# Schematic.net
KiCad netlist of a schematic drawn in EAGLE
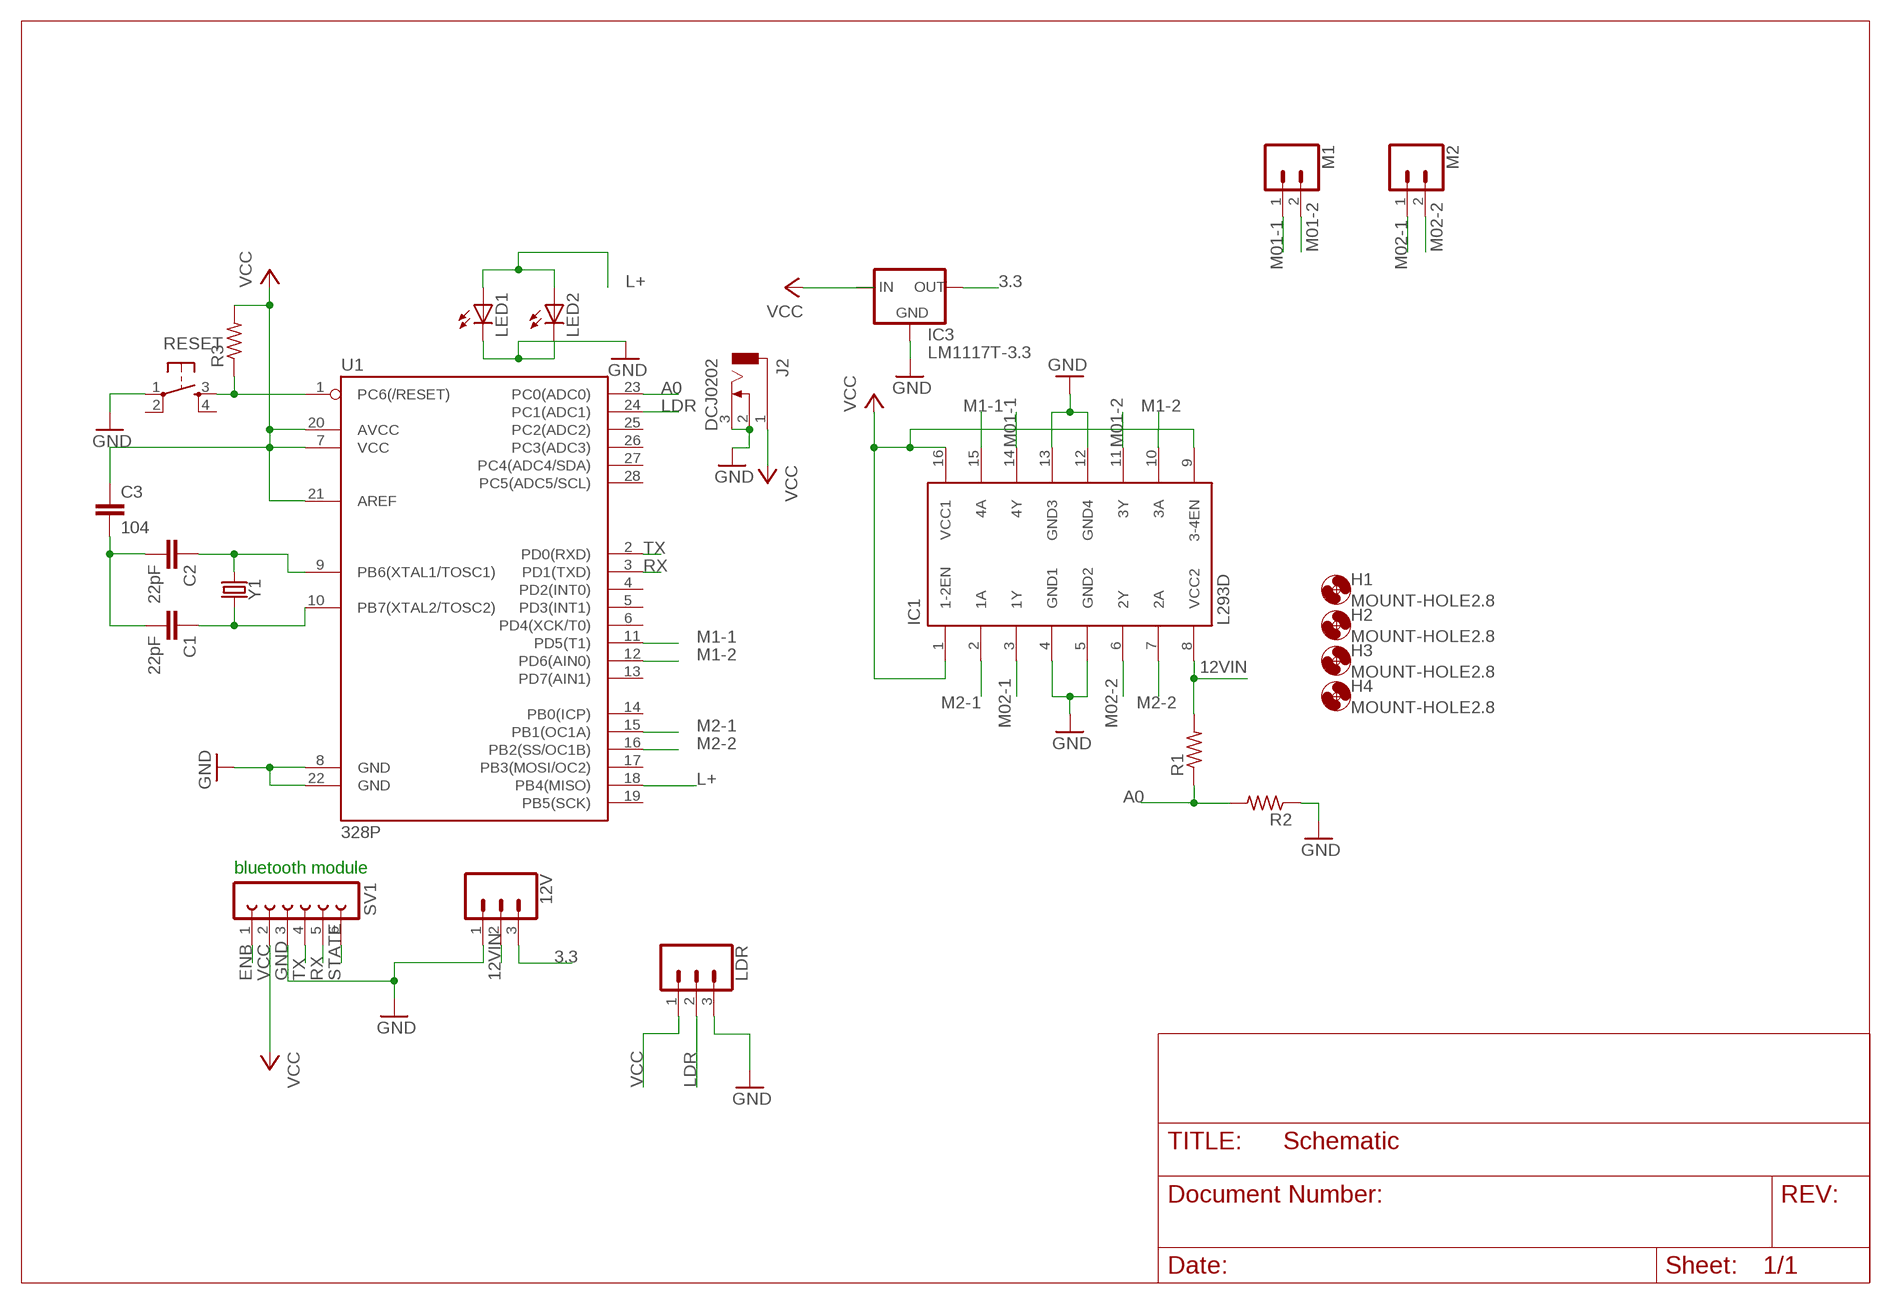
[diagram p0: schematic, sheet 1]

(export (version "E")
  (design (tool "Eeschema 10.0.6"))
  (components
    (comp (ref "12V")
      (value "CONN_03")
      (footprint "eagle-import:1X03")
      (libsource (lib "eagle-import") (part "CONN_03"))
    )
    (comp (ref "C1")
      (value "22pF")
      (footprint "eagle-import:CAP-PTH-2.54")
      (libsource (lib "eagle-import") (part "22PF-PTH-2.54MM-200V-5%"))
    )
    (comp (ref "C2")
      (value "22pF")
      (footprint "eagle-import:CAP-PTH-2.54")
      (libsource (lib "eagle-import") (part "22PF-PTH-2.54MM-200V-5%"))
    )
    (comp (ref "C3")
      (value "104")
      (footprint "eagle-import:CAP-PTH-2.54")
      (libsource (lib "eagle-import") (part "22PF-PTH-2.54MM-200V-5%"))
    )
    (comp (ref "H1")
      (value "MOUNT-HOLE2.8")
      (footprint "eagle-import:2,8")
      (libsource (lib "eagle-import") (part "MOUNT-HOLE2.8"))
    )
    (comp (ref "H2")
      (value "MOUNT-HOLE2.8")
      (footprint "eagle-import:2,8")
      (libsource (lib "eagle-import") (part "MOUNT-HOLE2.8"))
    )
    (comp (ref "H3")
      (value "MOUNT-HOLE2.8")
      (footprint "eagle-import:2,8")
      (libsource (lib "eagle-import") (part "MOUNT-HOLE2.8"))
    )
    (comp (ref "H4")
      (value "MOUNT-HOLE2.8")
      (footprint "eagle-import:2,8")
      (libsource (lib "eagle-import") (part "MOUNT-HOLE2.8"))
    )
    (comp (ref "IC1")
      (value "L293D")
      (footprint "eagle-import:DIL16")
      (libsource (lib "eagle-import") (part "L293D"))
    )
    (comp (ref "IC3")
      (value "LM1117T-3.3")
      (footprint "eagle-import:TO220")
      (libsource (lib "eagle-import") (part "LM1117T-3.3"))
    )
    (comp (ref "J2")
      (value "DCJ0202")
      (footprint "eagle-import:DCJ0202")
      (libsource (lib "eagle-import") (part "DCJ0202"))
    )
    (comp (ref "LDR")
      (value "CONN_03")
      (footprint "eagle-import:1X03")
      (libsource (lib "eagle-import") (part "CONN_03"))
    )
    (comp (ref "LED1")
      (value "LED5MM")
      (footprint "eagle-import:LED5MM")
      (libsource (lib "eagle-import") (part "LED5MM"))
    )
    (comp (ref "LED2")
      (value "LED5MM")
      (footprint "eagle-import:LED5MM")
      (libsource (lib "eagle-import") (part "LED5MM"))
    )
    (comp (ref "M1")
      (value "CONN_023.5MM")
      (footprint "eagle-import:SCREWTERMINAL-3.5MM-2")
      (libsource (lib "eagle-import") (part "CONN_023.5MM"))
    )
    (comp (ref "M2")
      (value "CONN_023.5MM")
      (footprint "eagle-import:SCREWTERMINAL-3.5MM-2")
      (libsource (lib "eagle-import") (part "CONN_023.5MM"))
    )
    (comp (ref "R1")
      (value "R-US_0204/7")
      (footprint "eagle-import:0204_7")
      (libsource (lib "eagle-import") (part "R-US_0204/7"))
    )
    (comp (ref "R2")
      (value "R-US_0204/7")
      (footprint "eagle-import:0204_7")
      (libsource (lib "eagle-import") (part "R-US_0204/7"))
    )
    (comp (ref "R3")
      (value "R-US_0204/7")
      (footprint "eagle-import:0204_7")
      (libsource (lib "eagle-import") (part "R-US_0204/7"))
    )
    (comp (ref "RESET")
      (value "TAC_SWITCHPTH")
      (footprint "eagle-import:TACTILE-PTH")
      (libsource (lib "eagle-import") (part "TAC_SWITCHPTH"))
    )
    (comp (ref "SV1")
      (value "FE06-1")
      (footprint "eagle-import:FE06")
      (libsource (lib "eagle-import") (part "FE06-1"))
    )
    (comp (ref "U1")
      (value "328P")
      (footprint "eagle-import:DIP28")
      (libsource (lib "eagle-import") (part "ATMEGA328P_PDIP"))
    )
    (comp (ref "Y1")
      (value "CRYSTALPTH-HC49US")
      (footprint "eagle-import:HC49US")
      (libsource (lib "eagle-import") (part "CRYSTALPTH-HC49US"))
    )
  )
  (nets
    (net (code "1") (name "/3.3") (class "Default")
      (node (ref "12V") (pin "3") (pinfunction "3_3") (pintype "passive"))
      (node (ref "IC3") (pin "2") (pinfunction "OUT_2") (pintype "passive"))
    )
    (net (code "2") (name "/12VIN") (class "Default")
      (node (ref "12V") (pin "2") (pinfunction "2_2") (pintype "passive"))
      (node (ref "IC1") (pin "8") (pinfunction "VCC2_8") (pintype "power_in"))
      (node (ref "R1") (pin "2") (pinfunction "2_2") (pintype "passive"))
    )
    (net (code "3") (name "/A0") (class "Default")
      (node (ref "R1") (pin "1") (pinfunction "1_1") (pintype "passive"))
      (node (ref "R2") (pin "2") (pinfunction "2_2") (pintype "passive"))
      (node (ref "U1") (pin "23") (pinfunction "PC0(ADC0)_23") (pintype "bidirectional"))
    )
    (net (code "4") (name "/ENB") (class "Default")
      (node (ref "SV1") (pin "1") (pinfunction "1_1") (pintype "passive"))
    )
    (net (code "5") (name "/L+") (class "Default")
      (node (ref "LED1") (pin "A") (pinfunction "A_A") (pintype "passive"))
      (node (ref "LED2") (pin "A") (pinfunction "A_A") (pintype "passive"))
      (node (ref "U1") (pin "18") (pinfunction "PB4(MISO)_18") (pintype "bidirectional"))
    )
    (net (code "6") (name "/LDR") (class "Default")
      (node (ref "LDR") (pin "2") (pinfunction "2_2") (pintype "passive"))
      (node (ref "U1") (pin "24") (pinfunction "PC1(ADC1)_24") (pintype "bidirectional"))
    )
    (net (code "7") (name "/M01-1") (class "Default")
      (node (ref "IC1") (pin "14") (pinfunction "4Y_14") (pintype "output"))
      (node (ref "M1") (pin "1") (pinfunction "1_1") (pintype "passive"))
    )
    (net (code "8") (name "/M1-1") (class "Default")
      (node (ref "IC1") (pin "15") (pinfunction "4A_15") (pintype "input"))
      (node (ref "U1") (pin "11") (pinfunction "PD5(T1)_11") (pintype "bidirectional"))
    )
    (net (code "9") (name "/M01-2") (class "Default")
      (node (ref "IC1") (pin "11") (pinfunction "3Y_11") (pintype "output"))
      (node (ref "M1") (pin "2") (pinfunction "2_2") (pintype "passive"))
    )
    (net (code "10") (name "/M1-2") (class "Default")
      (node (ref "IC1") (pin "10") (pinfunction "3A_10") (pintype "input"))
      (node (ref "U1") (pin "12") (pinfunction "PD6(AIN0)_12") (pintype "bidirectional"))
    )
    (net (code "11") (name "/M02-1") (class "Default")
      (node (ref "IC1") (pin "3") (pinfunction "1Y_3") (pintype "output"))
      (node (ref "M2") (pin "1") (pinfunction "1_1") (pintype "passive"))
    )
    (net (code "12") (name "/M2-1") (class "Default")
      (node (ref "IC1") (pin "2") (pinfunction "1A_2") (pintype "input"))
      (node (ref "U1") (pin "15") (pinfunction "PB1(OC1A)_15") (pintype "bidirectional"))
    )
    (net (code "13") (name "/M02-2") (class "Default")
      (node (ref "IC1") (pin "6") (pinfunction "2Y_6") (pintype "output"))
      (node (ref "M2") (pin "2") (pinfunction "2_2") (pintype "passive"))
    )
    (net (code "14") (name "/M2-2") (class "Default")
      (node (ref "IC1") (pin "7") (pinfunction "2A_7") (pintype "input"))
      (node (ref "U1") (pin "16") (pinfunction "PB2(SS/OC1B)_16") (pintype "bidirectional"))
    )
    (net (code "15") (name "/RX") (class "Default")
      (node (ref "SV1") (pin "5") (pinfunction "5_5") (pintype "passive"))
      (node (ref "U1") (pin "3") (pinfunction "PD1(TXD)_3") (pintype "bidirectional"))
    )
    (net (code "16") (name "/STATE") (class "Default")
      (node (ref "SV1") (pin "6") (pinfunction "6_6") (pintype "passive"))
    )
    (net (code "17") (name "/TX") (class "Default")
      (node (ref "SV1") (pin "4") (pinfunction "4_4") (pintype "passive"))
      (node (ref "U1") (pin "2") (pinfunction "PD0(RXD)_2") (pintype "bidirectional"))
    )
    (net (code "18") (name "GND") (class "Default")
      (node (ref "12V") (pin "1") (pinfunction "1_1") (pintype "passive"))
      (node (ref "IC1") (pin "12") (pinfunction "GND4_12") (pintype "power_in"))
      (node (ref "IC1") (pin "13") (pinfunction "GND3_13") (pintype "power_in"))
      (node (ref "IC1") (pin "4") (pinfunction "GND1_4") (pintype "power_in"))
      (node (ref "IC1") (pin "5") (pinfunction "GND2_5") (pintype "power_in"))
      (node (ref "IC3") (pin "1") (pinfunction "GND_1") (pintype "input"))
      (node (ref "J2") (pin "2") (pinfunction "2_2") (pintype "passive"))
      (node (ref "J2") (pin "3") (pinfunction "3_3") (pintype "passive"))
      (node (ref "LDR") (pin "3") (pinfunction "3_3") (pintype "passive"))
      (node (ref "LED1") (pin "K") (pinfunction "C_K") (pintype "passive"))
      (node (ref "LED2") (pin "K") (pinfunction "C_K") (pintype "passive"))
      (node (ref "R2") (pin "1") (pinfunction "1_1") (pintype "passive"))
      (node (ref "RESET") (pin "1") (pinfunction "1_1") (pintype "passive"))
      (node (ref "SV1") (pin "3") (pinfunction "3_3") (pintype "passive"))
      (node (ref "U1") (pin "22") (pinfunction "GND_22") (pintype "bidirectional"))
      (node (ref "U1") (pin "8") (pinfunction "GND_8") (pintype "bidirectional"))
    )
    (net (code "19") (name "Net-(C1-Pad2)") (class "Default")
      (node (ref "C1") (pin "2") (pinfunction "2_2") (pintype "passive"))
      (node (ref "C2") (pin "2") (pinfunction "2_2") (pintype "passive"))
      (node (ref "C3") (pin "2") (pinfunction "2_2") (pintype "passive"))
    )
    (net (code "20") (name "Net-(U1-PB6(XTAL1{slash}TOSC1))") (class "Default")
      (node (ref "C2") (pin "1") (pinfunction "1_1") (pintype "passive"))
      (node (ref "U1") (pin "9") (pinfunction "PB6(XTAL1/TOSC1)_9") (pintype "bidirectional"))
      (node (ref "Y1") (pin "1") (pinfunction "1_1") (pintype "passive"))
    )
    (net (code "21") (name "Net-(U1-PB7(XTAL2{slash}TOSC2))") (class "Default")
      (node (ref "C1") (pin "1") (pinfunction "1_1") (pintype "passive"))
      (node (ref "U1") (pin "10") (pinfunction "PB7(XTAL2/TOSC2)_10") (pintype "bidirectional"))
      (node (ref "Y1") (pin "2") (pinfunction "2_2") (pintype "passive"))
    )
    (net (code "22") (name "Net-(U1-PC6({slash}RESET))") (class "Default")
      (node (ref "R3") (pin "1") (pinfunction "1_1") (pintype "passive"))
      (node (ref "RESET") (pin "3") (pinfunction "3_3") (pintype "passive"))
      (node (ref "U1") (pin "1") (pinfunction "PC6(/RESET)_1") (pintype "bidirectional"))
    )
    (net (code "23") (name "VCC") (class "Default")
      (node (ref "C3") (pin "1") (pinfunction "1_1") (pintype "passive"))
      (node (ref "IC1") (pin "1") (pinfunction "1-2EN_1") (pintype "input"))
      (node (ref "IC1") (pin "16") (pinfunction "VCC1_16") (pintype "power_in"))
      (node (ref "IC1") (pin "9") (pinfunction "3-4EN_9") (pintype "input"))
      (node (ref "IC3") (pin "3") (pinfunction "IN_3") (pintype "input"))
      (node (ref "J2") (pin "1") (pinfunction "1_1") (pintype "passive"))
      (node (ref "LDR") (pin "1") (pinfunction "1_1") (pintype "passive"))
      (node (ref "R3") (pin "2") (pinfunction "2_2") (pintype "passive"))
      (node (ref "SV1") (pin "2") (pinfunction "2_2") (pintype "passive"))
      (node (ref "U1") (pin "20") (pinfunction "AVCC_20") (pintype "bidirectional"))
      (node (ref "U1") (pin "21") (pinfunction "AREF_21") (pintype "bidirectional"))
      (node (ref "U1") (pin "7") (pinfunction "VCC_7") (pintype "bidirectional"))
    )
    (net (code "24") (name "unconnected-(RESET-Pad2)") (class "Default")
      (node (ref "RESET") (pin "2") (pinfunction "2_2") (pintype "passive"))
    )
    (net (code "25") (name "unconnected-(RESET-Pad4)") (class "Default")
      (node (ref "RESET") (pin "4") (pinfunction "4_4") (pintype "passive"))
    )
    (net (code "26") (name "unconnected-(U1-PB0(ICP)-Pad14)") (class "Default")
      (node (ref "U1") (pin "14") (pinfunction "PB0(ICP)_14") (pintype "bidirectional"))
    )
    (net (code "27") (name "unconnected-(U1-PB3(MOSI{slash}OC2)-Pad17)") (class "Default")
      (node (ref "U1") (pin "17") (pinfunction "PB3(MOSI/OC2)_17") (pintype "bidirectional"))
    )
    (net (code "28") (name "unconnected-(U1-PB5(SCK)-Pad19)") (class "Default")
      (node (ref "U1") (pin "19") (pinfunction "PB5(SCK)_19") (pintype "bidirectional"))
    )
    (net (code "29") (name "unconnected-(U1-PC2(ADC2)-Pad25)") (class "Default")
      (node (ref "U1") (pin "25") (pinfunction "PC2(ADC2)_25") (pintype "bidirectional"))
    )
    (net (code "30") (name "unconnected-(U1-PC3(ADC3)-Pad26)") (class "Default")
      (node (ref "U1") (pin "26") (pinfunction "PC3(ADC3)_26") (pintype "bidirectional"))
    )
    (net (code "31") (name "unconnected-(U1-PC4(ADC4{slash}SDA)-Pad27)") (class "Default")
      (node (ref "U1") (pin "27") (pinfunction "PC4(ADC4/SDA)_27") (pintype "bidirectional"))
    )
    (net (code "32") (name "unconnected-(U1-PC5(ADC5{slash}SCL)-Pad28)") (class "Default")
      (node (ref "U1") (pin "28") (pinfunction "PC5(ADC5/SCL)_28") (pintype "bidirectional"))
    )
    (net (code "33") (name "unconnected-(U1-PD2(INT0)-Pad4)") (class "Default")
      (node (ref "U1") (pin "4") (pinfunction "PD2(INT0)_4") (pintype "bidirectional"))
    )
    (net (code "34") (name "unconnected-(U1-PD3(INT1)-Pad5)") (class "Default")
      (node (ref "U1") (pin "5") (pinfunction "PD3(INT1)_5") (pintype "bidirectional"))
    )
    (net (code "35") (name "unconnected-(U1-PD4(XCK{slash}T0)-Pad6)") (class "Default")
      (node (ref "U1") (pin "6") (pinfunction "PD4(XCK/T0)_6") (pintype "bidirectional"))
    )
    (net (code "36") (name "unconnected-(U1-PD7(AIN1)-Pad13)") (class "Default")
      (node (ref "U1") (pin "13") (pinfunction "PD7(AIN1)_13") (pintype "bidirectional"))
    )
  )
)
